# QCopterRC_ETH_Sch.net
KiCad netlist of a schematic drawn in Altium Designer
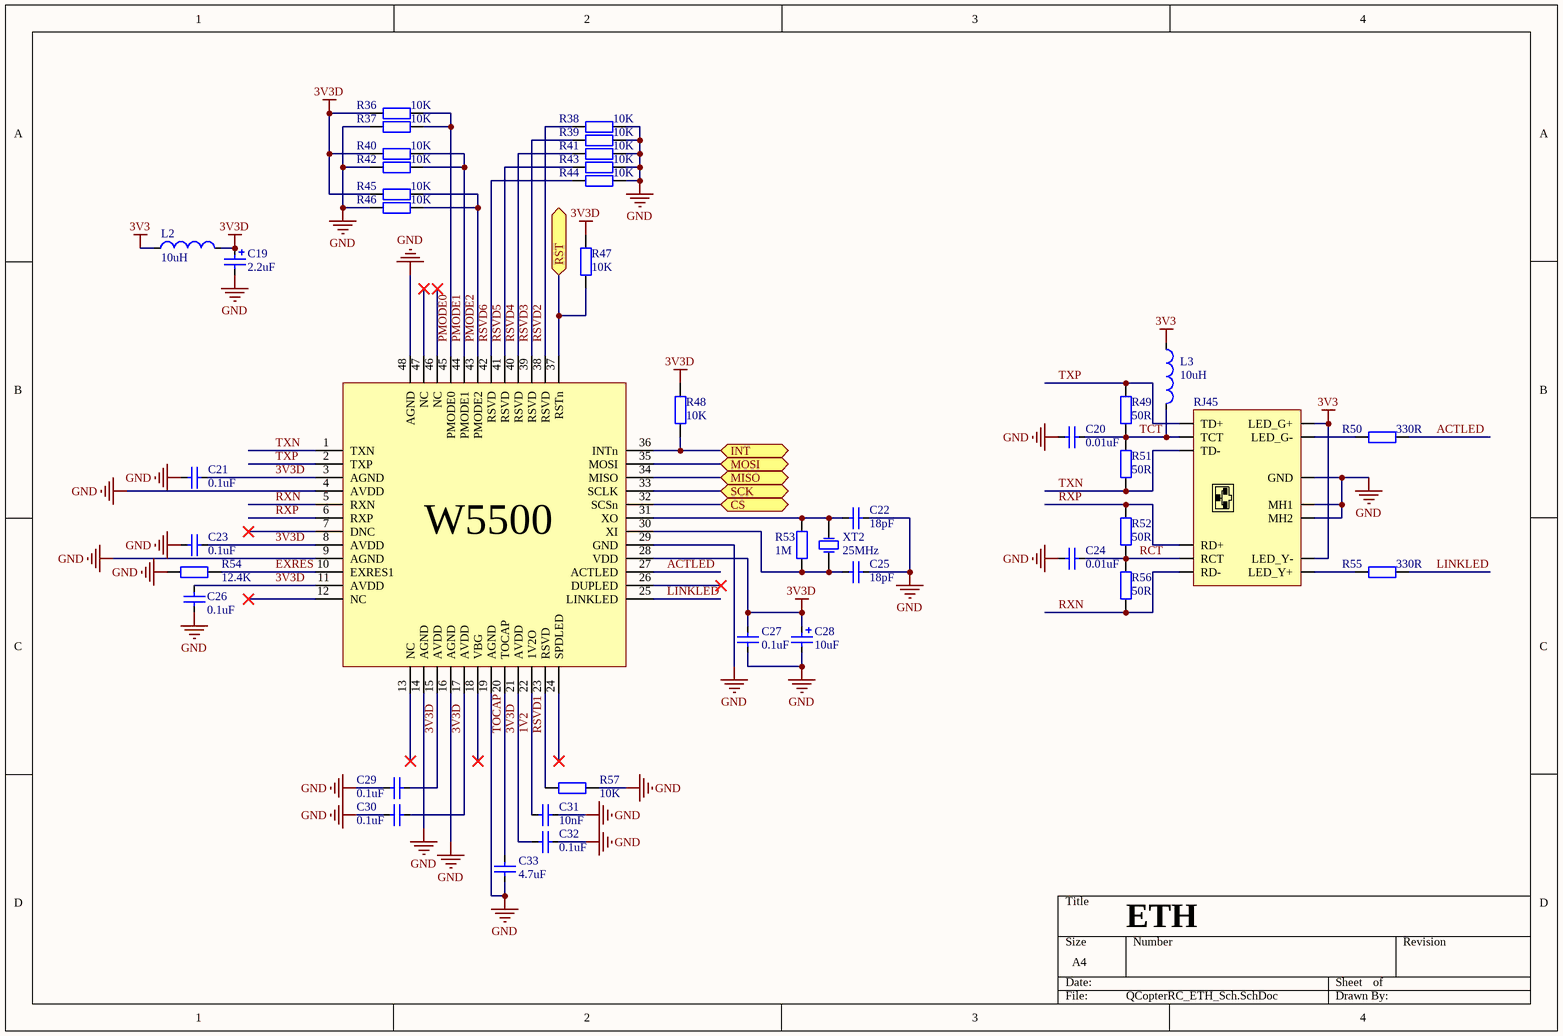
[diagram p0: QCopterRC_ETH_Sch.SchDoc]

(export (version "E")
  (design (tool "Eeschema 10.0.6"))
  (components
    (comp (ref "C19")
      (value "2.2uF")
      (footprint "PCB_Passive:CAP_TAN_P0805")
      (description "Capacitor")
      (fields (field (name "Comment") "Cap_Tan_0805"))
      (libsource (lib "SCH_Passive") (part "Cap_Tan_0805"))
    )
    (comp (ref "C20")
      (value "0.01uF")
      (footprint "PCB_Passive:CAP_0603")
      (description "Capacitor")
      (fields (field (name "Comment") "Cap_0603"))
      (libsource (lib "SCH_Passive") (part "Cap_0603"))
    )
    (comp (ref "C21")
      (value "0.1uF")
      (footprint "PCB_Passive:CAP_0603")
      (description "Capacitor")
      (fields (field (name "Comment") "Cap_0603"))
      (libsource (lib "SCH_Passive") (part "Cap_0603"))
    )
    (comp (ref "C22")
      (value "18pF")
      (footprint "PCB_Passive:CAP_0603")
      (description "Capacitor")
      (fields (field (name "Comment") "Cap_0603"))
      (libsource (lib "SCH_Passive") (part "Cap_0603"))
    )
    (comp (ref "C23")
      (value "0.1uF")
      (footprint "PCB_Passive:CAP_0603")
      (description "Capacitor")
      (fields (field (name "Comment") "Cap_0603"))
      (libsource (lib "SCH_Passive") (part "Cap_0603"))
    )
    (comp (ref "C24")
      (value "0.01uF")
      (footprint "PCB_Passive:CAP_0603")
      (description "Capacitor")
      (fields (field (name "Comment") "Cap_0603"))
      (libsource (lib "SCH_Passive") (part "Cap_0603"))
    )
    (comp (ref "C25")
      (value "18pF")
      (footprint "PCB_Passive:CAP_0603")
      (description "Capacitor")
      (fields (field (name "Comment") "Cap_0603"))
      (libsource (lib "SCH_Passive") (part "Cap_0603"))
    )
    (comp (ref "C26")
      (value "0.1uF")
      (footprint "PCB_Passive:CAP_0603")
      (description "Capacitor")
      (fields (field (name "Comment") "Cap_0603"))
      (libsource (lib "SCH_Passive") (part "Cap_0603"))
    )
    (comp (ref "C27")
      (value "0.1uF")
      (footprint "PCB_Passive:CAP_0603")
      (description "Capacitor")
      (fields (field (name "Comment") "Cap_0603"))
      (libsource (lib "SCH_Passive") (part "Cap_0603"))
    )
    (comp (ref "C28")
      (value "10uF")
      (footprint "PCB_Passive:CAP_TAN_B1210")
      (description "Capacitor")
      (fields (field (name "Comment") "Cap_Tan_1210"))
      (libsource (lib "SCH_Passive") (part "Cap_Tan_1210"))
    )
    (comp (ref "C29")
      (value "0.1uF")
      (footprint "PCB_Passive:CAP_0603")
      (description "Capacitor")
      (fields (field (name "Comment") "Cap_0603"))
      (libsource (lib "SCH_Passive") (part "Cap_0603"))
    )
    (comp (ref "C30")
      (value "0.1uF")
      (footprint "PCB_Passive:CAP_0603")
      (description "Capacitor")
      (fields (field (name "Comment") "Cap_0603"))
      (libsource (lib "SCH_Passive") (part "Cap_0603"))
    )
    (comp (ref "C31")
      (value "10nF")
      (footprint "PCB_Passive:CAP_0603")
      (description "Capacitor")
      (fields (field (name "Comment") "Cap_0603"))
      (libsource (lib "SCH_Passive") (part "Cap_0603"))
    )
    (comp (ref "C32")
      (value "0.1uF")
      (footprint "PCB_Passive:CAP_0603")
      (description "Capacitor")
      (fields (field (name "Comment") "Cap_0603"))
      (libsource (lib "SCH_Passive") (part "Cap_0603"))
    )
    (comp (ref "C33")
      (value "4.7uF")
      (footprint "PCB_Passive:CAP_0603")
      (description "Capacitor")
      (fields (field (name "Comment") "Cap_0603"))
      (libsource (lib "SCH_Passive") (part "Cap_0603"))
    )
    (comp (ref "L2")
      (value "10uH")
      (footprint "PCB_Passive:IND_0603")
      (description "Inductor")
      (fields (field (name "Comment") "Ind_0603"))
      (libsource (lib "SCH_Passive") (part "Ind_0603"))
    )
    (comp (ref "L3")
      (value "10uH")
      (footprint "PCB_Passive:IND_0603")
      (description "Inductor")
      (fields (field (name "Comment") "Ind_0603"))
      (libsource (lib "SCH_Passive") (part "Ind_0603"))
    )
    (comp (ref "R36")
      (value "10K")
      (footprint "PCB_Passive:RES_0603")
      (description "Resistor")
      (fields (field (name "Comment") "Res_0603"))
      (libsource (lib "SCH_Passive") (part "Res_0603"))
    )
    (comp (ref "R37")
      (value "10K")
      (footprint "PCB_Passive:RES_0603")
      (description "Resistor")
      (fields (field (name "Comment") "Res_0603"))
      (libsource (lib "SCH_Passive") (part "Res_0603"))
    )
    (comp (ref "R38")
      (value "10K")
      (footprint "PCB_Passive:RES_0603")
      (description "Resistor")
      (fields (field (name "Comment") "Res_0603"))
      (libsource (lib "SCH_Passive") (part "Res_0603"))
    )
    (comp (ref "R39")
      (value "10K")
      (footprint "PCB_Passive:RES_0603")
      (description "Resistor")
      (fields (field (name "Comment") "Res_0603"))
      (libsource (lib "SCH_Passive") (part "Res_0603"))
    )
    (comp (ref "R40")
      (value "10K")
      (footprint "PCB_Passive:RES_0603")
      (description "Resistor")
      (fields (field (name "Comment") "Res_0603"))
      (libsource (lib "SCH_Passive") (part "Res_0603"))
    )
    (comp (ref "R41")
      (value "10K")
      (footprint "PCB_Passive:RES_0603")
      (description "Resistor")
      (fields (field (name "Comment") "Res_0603"))
      (libsource (lib "SCH_Passive") (part "Res_0603"))
    )
    (comp (ref "R42")
      (value "10K")
      (footprint "PCB_Passive:RES_0603")
      (description "Resistor")
      (fields (field (name "Comment") "Res_0603"))
      (libsource (lib "SCH_Passive") (part "Res_0603"))
    )
    (comp (ref "R43")
      (value "10K")
      (footprint "PCB_Passive:RES_0603")
      (description "Resistor")
      (fields (field (name "Comment") "Res_0603"))
      (libsource (lib "SCH_Passive") (part "Res_0603"))
    )
    (comp (ref "R44")
      (value "10K")
      (footprint "PCB_Passive:RES_0603")
      (description "Resistor")
      (fields (field (name "Comment") "Res_0603"))
      (libsource (lib "SCH_Passive") (part "Res_0603"))
    )
    (comp (ref "R45")
      (value "10K")
      (footprint "PCB_Passive:RES_0603")
      (description "Resistor")
      (fields (field (name "Comment") "Res_0603"))
      (libsource (lib "SCH_Passive") (part "Res_0603"))
    )
    (comp (ref "R46")
      (value "10K")
      (footprint "PCB_Passive:RES_0603")
      (description "Resistor")
      (fields (field (name "Comment") "Res_0603"))
      (libsource (lib "SCH_Passive") (part "Res_0603"))
    )
    (comp (ref "R47")
      (value "10K")
      (footprint "PCB_Passive:RES_0603")
      (description "Resistor")
      (fields (field (name "Comment") "Res_0603"))
      (libsource (lib "") (part "Res_0603_1"))
    )
    (comp (ref "R48")
      (value "10K")
      (footprint "PCB_Passive:RES_0603")
      (description "Resistor")
      (fields (field (name "Comment") "Res_0603"))
      (libsource (lib "") (part "Res_0603_1"))
    )
    (comp (ref "R49")
      (value "50R")
      (footprint "PCB_Passive:RES_0603")
      (description "Resistor")
      (fields (field (name "Comment") "Res_0603"))
      (libsource (lib "") (part "Res_0603_1"))
    )
    (comp (ref "R50")
      (value "330R")
      (footprint "PCB_Passive:RES_0603")
      (description "Resistor")
      (fields (field (name "Comment") "Res_0603"))
      (libsource (lib "SCH_Passive") (part "Res_0603"))
    )
    (comp (ref "R51")
      (value "50R")
      (footprint "PCB_Passive:RES_0603")
      (description "Resistor")
      (fields (field (name "Comment") "Res_0603"))
      (libsource (lib "") (part "Res_0603_1"))
    )
    (comp (ref "R52")
      (value "50R")
      (footprint "PCB_Passive:RES_0603")
      (description "Resistor")
      (fields (field (name "Comment") "Res_0603"))
      (libsource (lib "") (part "Res_0603_1"))
    )
    (comp (ref "R53")
      (value "1M")
      (footprint "PCB_Passive:RES_0603")
      (description "Resistor")
      (fields (field (name "Comment") "Res_0603"))
      (libsource (lib "") (part "Res_0603_1"))
    )
    (comp (ref "R54")
      (value "12.4K")
      (footprint "PCB_Passive:RES_0603")
      (description "Resistor")
      (fields (field (name "Comment") "Res_0603"))
      (libsource (lib "SCH_Passive") (part "Res_0603"))
    )
    (comp (ref "R55")
      (value "330R")
      (footprint "PCB_Passive:RES_0603")
      (description "Resistor")
      (fields (field (name "Comment") "Res_0603"))
      (libsource (lib "SCH_Passive") (part "Res_0603"))
    )
    (comp (ref "R56")
      (value "50R")
      (footprint "PCB_Passive:RES_0603")
      (description "Resistor")
      (fields (field (name "Comment") "Res_0603"))
      (libsource (lib "") (part "Res_0603_1"))
    )
    (comp (ref "R57")
      (value "10K")
      (footprint "PCB_Passive:RES_0603")
      (description "Resistor")
      (fields (field (name "Comment") "Res_0603"))
      (libsource (lib "") (part "Res_0603_2"))
    )
    (comp (ref "RJ45")
      (value "RJ45")
      (footprint "PCB_Connector:RJ-45_LED")
      (description "ETH")
      (libsource (lib "SCH_Connector") (part "RJ45"))
    )
    (comp (ref "W5500")
      (value "W5500")
      (footprint "PCB_IC:W5500")
      (description "Ethernet")
      (libsource (lib "SCH_IC") (part "W5500"))
    )
    (comp (ref "XT2")
      (value "25MHz")
      (footprint "PCB_Oscillator:XTAL_5032")
      (description "Crystal Oscillator")
      (fields (field (name "Comment") "XTAL_5032") (field (name "PUBLISHER") "Altium Limited"))
      (libsource (lib "SCH_Oscillator") (part "XTAL_5032"))
    )
  )
  (nets
    (net (code "1") (name "/1V2") (class "Default")
      (node (ref "C31") (pin "2") (pinfunction "2_2") (pintype "passive"))
      (node (ref "W5500") (pin "22") (pinfunction "1V2O_22") (pintype "passive"))
    )
    (net (code "2") (name "/ACTLED") (class "Default")
      (node (ref "R50") (pin "1") (pinfunction "1_1") (pintype "passive"))
      (node (ref "W5500") (pin "27") (pinfunction "ACTLED_27") (pintype "passive"))
    )
    (net (code "3") (name "/CS") (class "Default")
      (node (ref "W5500") (pin "32") (pinfunction "SCSn_32") (pintype "passive"))
    )
    (net (code "5") (name "/EXRES") (class "Default")
      (node (ref "R54") (pin "1") (pinfunction "1_1") (pintype "passive"))
      (node (ref "W5500") (pin "10") (pinfunction "EXRES1_10") (pintype "passive"))
    )
    (net (code "6") (name "/INT") (class "Default")
      (node (ref "R48") (pin "1") (pinfunction "1_1") (pintype "passive"))
      (node (ref "W5500") (pin "36") (pinfunction "INTn_36") (pintype "passive"))
    )
    (net (code "7") (name "/LINKLED") (class "Default")
      (node (ref "R55") (pin "1") (pinfunction "1_1") (pintype "passive"))
      (node (ref "W5500") (pin "25") (pinfunction "LINKLED_25") (pintype "passive"))
    )
    (net (code "8") (name "/MISO") (class "Default")
      (node (ref "W5500") (pin "34") (pinfunction "MISO_34") (pintype "passive"))
    )
    (net (code "9") (name "/MOSI") (class "Default")
      (node (ref "W5500") (pin "35") (pinfunction "MOSI_35") (pintype "passive"))
    )
    (net (code "10") (name "/PMODE0") (class "Default")
      (node (ref "R36") (pin "1") (pinfunction "1_1") (pintype "passive"))
      (node (ref "R37") (pin "1") (pinfunction "1_1") (pintype "passive"))
      (node (ref "W5500") (pin "45") (pinfunction "PMODE0_45") (pintype "passive"))
    )
    (net (code "11") (name "/PMODE1") (class "Default")
      (node (ref "R40") (pin "1") (pinfunction "1_1") (pintype "passive"))
      (node (ref "R42") (pin "1") (pinfunction "1_1") (pintype "passive"))
      (node (ref "W5500") (pin "44") (pinfunction "PMODE1_44") (pintype "passive"))
    )
    (net (code "12") (name "/PMODE2") (class "Default")
      (node (ref "R45") (pin "1") (pinfunction "1_1") (pintype "passive"))
      (node (ref "R46") (pin "1") (pinfunction "1_1") (pintype "passive"))
      (node (ref "W5500") (pin "43") (pinfunction "PMODE2_43") (pintype "passive"))
    )
    (net (code "13") (name "/RCT") (class "Default")
      (node (ref "C24") (pin "2") (pinfunction "2_2") (pintype "passive"))
      (node (ref "R52") (pin "1") (pinfunction "1_1") (pintype "passive"))
      (node (ref "R56") (pin "2") (pinfunction "2_2") (pintype "passive"))
      (node (ref "RJ45") (pin "5") (pinfunction "RCT_5") (pintype "passive"))
    )
    (net (code "14") (name "/RST") (class "Default")
      (node (ref "R47") (pin "1") (pinfunction "1_1") (pintype "passive"))
      (node (ref "W5500") (pin "37") (pinfunction "RSTn_37") (pintype "passive"))
    )
    (net (code "15") (name "/RSVD1") (class "Default")
      (node (ref "R57") (pin "1") (pinfunction "1_1") (pintype "passive"))
      (node (ref "W5500") (pin "23") (pinfunction "RSVD_23") (pintype "passive"))
    )
    (net (code "16") (name "/RSVD2") (class "Default")
      (node (ref "R38") (pin "2") (pinfunction "2_2") (pintype "passive"))
      (node (ref "W5500") (pin "38") (pinfunction "RSVD_38") (pintype "passive"))
    )
    (net (code "17") (name "/RSVD3") (class "Default")
      (node (ref "R39") (pin "2") (pinfunction "2_2") (pintype "passive"))
      (node (ref "W5500") (pin "39") (pinfunction "RSVD_39") (pintype "passive"))
    )
    (net (code "18") (name "/RSVD4") (class "Default")
      (node (ref "R41") (pin "2") (pinfunction "2_2") (pintype "passive"))
      (node (ref "W5500") (pin "40") (pinfunction "RSVD_40") (pintype "passive"))
    )
    (net (code "19") (name "/RSVD5") (class "Default")
      (node (ref "R43") (pin "2") (pinfunction "2_2") (pintype "passive"))
      (node (ref "W5500") (pin "41") (pinfunction "RSVD_41") (pintype "passive"))
    )
    (net (code "20") (name "/RSVD6") (class "Default")
      (node (ref "R44") (pin "2") (pinfunction "2_2") (pintype "passive"))
      (node (ref "W5500") (pin "42") (pinfunction "RSVD_42") (pintype "passive"))
    )
    (net (code "21") (name "/RXN") (class "Default")
      (node (ref "R56") (pin "1") (pinfunction "1_1") (pintype "passive"))
      (node (ref "RJ45") (pin "6") (pinfunction "RD-_6") (pintype "passive"))
      (node (ref "W5500") (pin "5") (pinfunction "RXN_5") (pintype "passive"))
    )
    (net (code "22") (name "/RXP") (class "Default")
      (node (ref "R52") (pin "2") (pinfunction "2_2") (pintype "passive"))
      (node (ref "RJ45") (pin "3") (pinfunction "RD+_3") (pintype "passive"))
      (node (ref "W5500") (pin "6") (pinfunction "RXP_6") (pintype "passive"))
    )
    (net (code "23") (name "/SCK") (class "Default")
      (node (ref "W5500") (pin "33") (pinfunction "SCLK_33") (pintype "passive"))
    )
    (net (code "24") (name "/TCT") (class "Default")
      (node (ref "C20") (pin "2") (pinfunction "2_2") (pintype "passive"))
      (node (ref "L3") (pin "2") (pinfunction "2_2") (pintype "passive"))
      (node (ref "R49") (pin "1") (pinfunction "1_1") (pintype "passive"))
      (node (ref "R51") (pin "2") (pinfunction "2_2") (pintype "passive"))
      (node (ref "RJ45") (pin "4") (pinfunction "TCT_4") (pintype "passive"))
    )
    (net (code "25") (name "/TOCAP") (class "Default")
      (node (ref "C33") (pin "2") (pinfunction "2_2") (pintype "passive"))
      (node (ref "W5500") (pin "20") (pinfunction "TOCAP_20") (pintype "passive"))
    )
    (net (code "26") (name "/TXN") (class "Default")
      (node (ref "R51") (pin "1") (pinfunction "1_1") (pintype "passive"))
      (node (ref "RJ45") (pin "2") (pinfunction "TD-_2") (pintype "passive"))
      (node (ref "W5500") (pin "1") (pinfunction "TXN_1") (pintype "passive"))
    )
    (net (code "27") (name "/TXP") (class "Default")
      (node (ref "R49") (pin "2") (pinfunction "2_2") (pintype "passive"))
      (node (ref "RJ45") (pin "1") (pinfunction "TD+_1") (pintype "passive"))
      (node (ref "W5500") (pin "2") (pinfunction "TXP_2") (pintype "passive"))
    )
    (net (code "28") (name "3V3") (class "Default")
      (node (ref "L2") (pin "1") (pinfunction "1_1") (pintype "passive"))
      (node (ref "L3") (pin "1") (pinfunction "1_1") (pintype "passive"))
      (node (ref "RJ45") (pin "11") (pinfunction "LED_Y-_11") (pintype "passive"))
      (node (ref "RJ45") (pin "9") (pinfunction "LED_G+_9") (pintype "passive"))
    )
    (net (code "29") (name "3V3D") (class "Default")
      (node (ref "C19") (pin "1") (pinfunction "1_1") (pintype "passive"))
      (node (ref "C21") (pin "2") (pinfunction "2_2") (pintype "passive"))
      (node (ref "C23") (pin "2") (pinfunction "2_2") (pintype "passive"))
      (node (ref "C26") (pin "2") (pinfunction "2_2") (pintype "passive"))
      (node (ref "C27") (pin "2") (pinfunction "2_2") (pintype "passive"))
      (node (ref "C28") (pin "1") (pinfunction "1_1") (pintype "passive"))
      (node (ref "C29") (pin "1") (pinfunction "1_1") (pintype "passive"))
      (node (ref "C30") (pin "1") (pinfunction "1_1") (pintype "passive"))
      (node (ref "C32") (pin "2") (pinfunction "2_2") (pintype "passive"))
      (node (ref "L2") (pin "2") (pinfunction "2_2") (pintype "passive"))
      (node (ref "R36") (pin "2") (pinfunction "2_2") (pintype "passive"))
      (node (ref "R40") (pin "2") (pinfunction "2_2") (pintype "passive"))
      (node (ref "R45") (pin "2") (pinfunction "2_2") (pintype "passive"))
      (node (ref "R47") (pin "2") (pinfunction "2_2") (pintype "passive"))
      (node (ref "R48") (pin "2") (pinfunction "2_2") (pintype "passive"))
      (node (ref "W5500") (pin "11") (pinfunction "AVDD_11") (pintype "passive"))
      (node (ref "W5500") (pin "15") (pinfunction "AVDD_15") (pintype "passive"))
      (node (ref "W5500") (pin "17") (pinfunction "AVDD_17") (pintype "passive"))
      (node (ref "W5500") (pin "21") (pinfunction "AVDD_21") (pintype "passive"))
      (node (ref "W5500") (pin "28") (pinfunction "VDD_28") (pintype "passive"))
      (node (ref "W5500") (pin "3") (pinfunction "AGND_3") (pintype "passive"))
      (node (ref "W5500") (pin "8") (pinfunction "AVDD_8") (pintype "passive"))
    )
    (net (code "30") (name "GND") (class "Default")
      (node (ref "C19") (pin "2") (pinfunction "2_2") (pintype "passive"))
      (node (ref "C20") (pin "1") (pinfunction "1_1") (pintype "passive"))
      (node (ref "C21") (pin "1") (pinfunction "1_1") (pintype "passive"))
      (node (ref "C22") (pin "1") (pinfunction "1_1") (pintype "passive"))
      (node (ref "C23") (pin "1") (pinfunction "1_1") (pintype "passive"))
      (node (ref "C24") (pin "1") (pinfunction "1_1") (pintype "passive"))
      (node (ref "C25") (pin "1") (pinfunction "1_1") (pintype "passive"))
      (node (ref "C26") (pin "1") (pinfunction "1_1") (pintype "passive"))
      (node (ref "C27") (pin "1") (pinfunction "1_1") (pintype "passive"))
      (node (ref "C28") (pin "2") (pinfunction "2_2") (pintype "passive"))
      (node (ref "C29") (pin "2") (pinfunction "2_2") (pintype "passive"))
      (node (ref "C30") (pin "2") (pinfunction "2_2") (pintype "passive"))
      (node (ref "C31") (pin "1") (pinfunction "1_1") (pintype "passive"))
      (node (ref "C32") (pin "1") (pinfunction "1_1") (pintype "passive"))
      (node (ref "C33") (pin "1") (pinfunction "1_1") (pintype "passive"))
      (node (ref "R37") (pin "2") (pinfunction "2_2") (pintype "passive"))
      (node (ref "R38") (pin "1") (pinfunction "1_1") (pintype "passive"))
      (node (ref "R39") (pin "1") (pinfunction "1_1") (pintype "passive"))
      (node (ref "R41") (pin "1") (pinfunction "1_1") (pintype "passive"))
      (node (ref "R42") (pin "2") (pinfunction "2_2") (pintype "passive"))
      (node (ref "R43") (pin "1") (pinfunction "1_1") (pintype "passive"))
      (node (ref "R44") (pin "1") (pinfunction "1_1") (pintype "passive"))
      (node (ref "R46") (pin "2") (pinfunction "2_2") (pintype "passive"))
      (node (ref "R54") (pin "2") (pinfunction "2_2") (pintype "passive"))
      (node (ref "R57") (pin "2") (pinfunction "2_2") (pintype "passive"))
      (node (ref "RJ45") (pin "13") (pinfunction "MH1_13") (pintype "passive"))
      (node (ref "RJ45") (pin "14") (pinfunction "MH2_14") (pintype "passive"))
      (node (ref "RJ45") (pin "8") (pinfunction "GND_8") (pintype "passive"))
      (node (ref "W5500") (pin "14") (pinfunction "AGND_14") (pintype "passive"))
      (node (ref "W5500") (pin "16") (pinfunction "AGND_16") (pintype "passive"))
      (node (ref "W5500") (pin "19") (pinfunction "AGND_19") (pintype "passive"))
      (node (ref "W5500") (pin "29") (pinfunction "GND_29") (pintype "passive"))
      (node (ref "W5500") (pin "4") (pinfunction "AVDD_4") (pintype "passive"))
      (node (ref "W5500") (pin "48") (pinfunction "AGND_48") (pintype "passive"))
      (node (ref "W5500") (pin "9") (pinfunction "AGND_9") (pintype "passive"))
    )
    (net (code "31") (name "Net-(RJ45-LED_G-)") (class "Default")
      (node (ref "R50") (pin "2") (pinfunction "2_2") (pintype "passive"))
      (node (ref "RJ45") (pin "10") (pinfunction "LED_G-_10") (pintype "passive"))
    )
    (net (code "32") (name "Net-(RJ45-LED_Y+)") (class "Default")
      (node (ref "R55") (pin "2") (pinfunction "2_2") (pintype "passive"))
      (node (ref "RJ45") (pin "12") (pinfunction "LED_Y+_12") (pintype "passive"))
    )
    (net (code "33") (name "Net-(W5500-XI)") (class "Default")
      (node (ref "C25") (pin "2") (pinfunction "2_2") (pintype "passive"))
      (node (ref "R53") (pin "1") (pinfunction "1_1") (pintype "passive"))
      (node (ref "W5500") (pin "30") (pinfunction "XI_30") (pintype "passive"))
      (node (ref "XT2") (pin "1") (pinfunction "OSC1_1") (pintype "passive"))
    )
    (net (code "34") (name "Net-(W5500-XO)") (class "Default")
      (node (ref "C22") (pin "2") (pinfunction "2_2") (pintype "passive"))
      (node (ref "R53") (pin "2") (pinfunction "2_2") (pintype "passive"))
      (node (ref "W5500") (pin "31") (pinfunction "XO_31") (pintype "passive"))
      (node (ref "XT2") (pin "2") (pinfunction "OSC2_2") (pintype "passive"))
    )
    (net (code "35") (name "unconnected-(W5500-DNC-Pad7)") (class "Default")
      (node (ref "W5500") (pin "7") (pinfunction "DNC_7") (pintype "passive+no_connect"))
    )
    (net (code "36") (name "unconnected-(W5500-DUPLED-Pad26)") (class "Default")
      (node (ref "W5500") (pin "26") (pinfunction "DUPLED_26") (pintype "passive+no_connect"))
    )
    (net (code "37") (name "unconnected-(W5500-NC-Pad12)") (class "Default")
      (node (ref "W5500") (pin "12") (pinfunction "NC_12") (pintype "passive+no_connect"))
    )
    (net (code "38") (name "unconnected-(W5500-NC-Pad13)") (class "Default")
      (node (ref "W5500") (pin "13") (pinfunction "NC_13") (pintype "passive+no_connect"))
    )
    (net (code "39") (name "unconnected-(W5500-NC-Pad46)") (class "Default")
      (node (ref "W5500") (pin "46") (pinfunction "NC_46") (pintype "passive+no_connect"))
    )
    (net (code "40") (name "unconnected-(W5500-NC-Pad47)") (class "Default")
      (node (ref "W5500") (pin "47") (pinfunction "NC_47") (pintype "passive+no_connect"))
    )
    (net (code "41") (name "unconnected-(W5500-SPDLED-Pad24)") (class "Default")
      (node (ref "W5500") (pin "24") (pinfunction "SPDLED_24") (pintype "passive+no_connect"))
    )
    (net (code "42") (name "unconnected-(W5500-VBG-Pad18)") (class "Default")
      (node (ref "W5500") (pin "18") (pinfunction "VBG_18") (pintype "passive+no_connect"))
    )
  )
)
